# PoE_Injector.net
KiCad netlist of a schematic drawn in Altium Designer
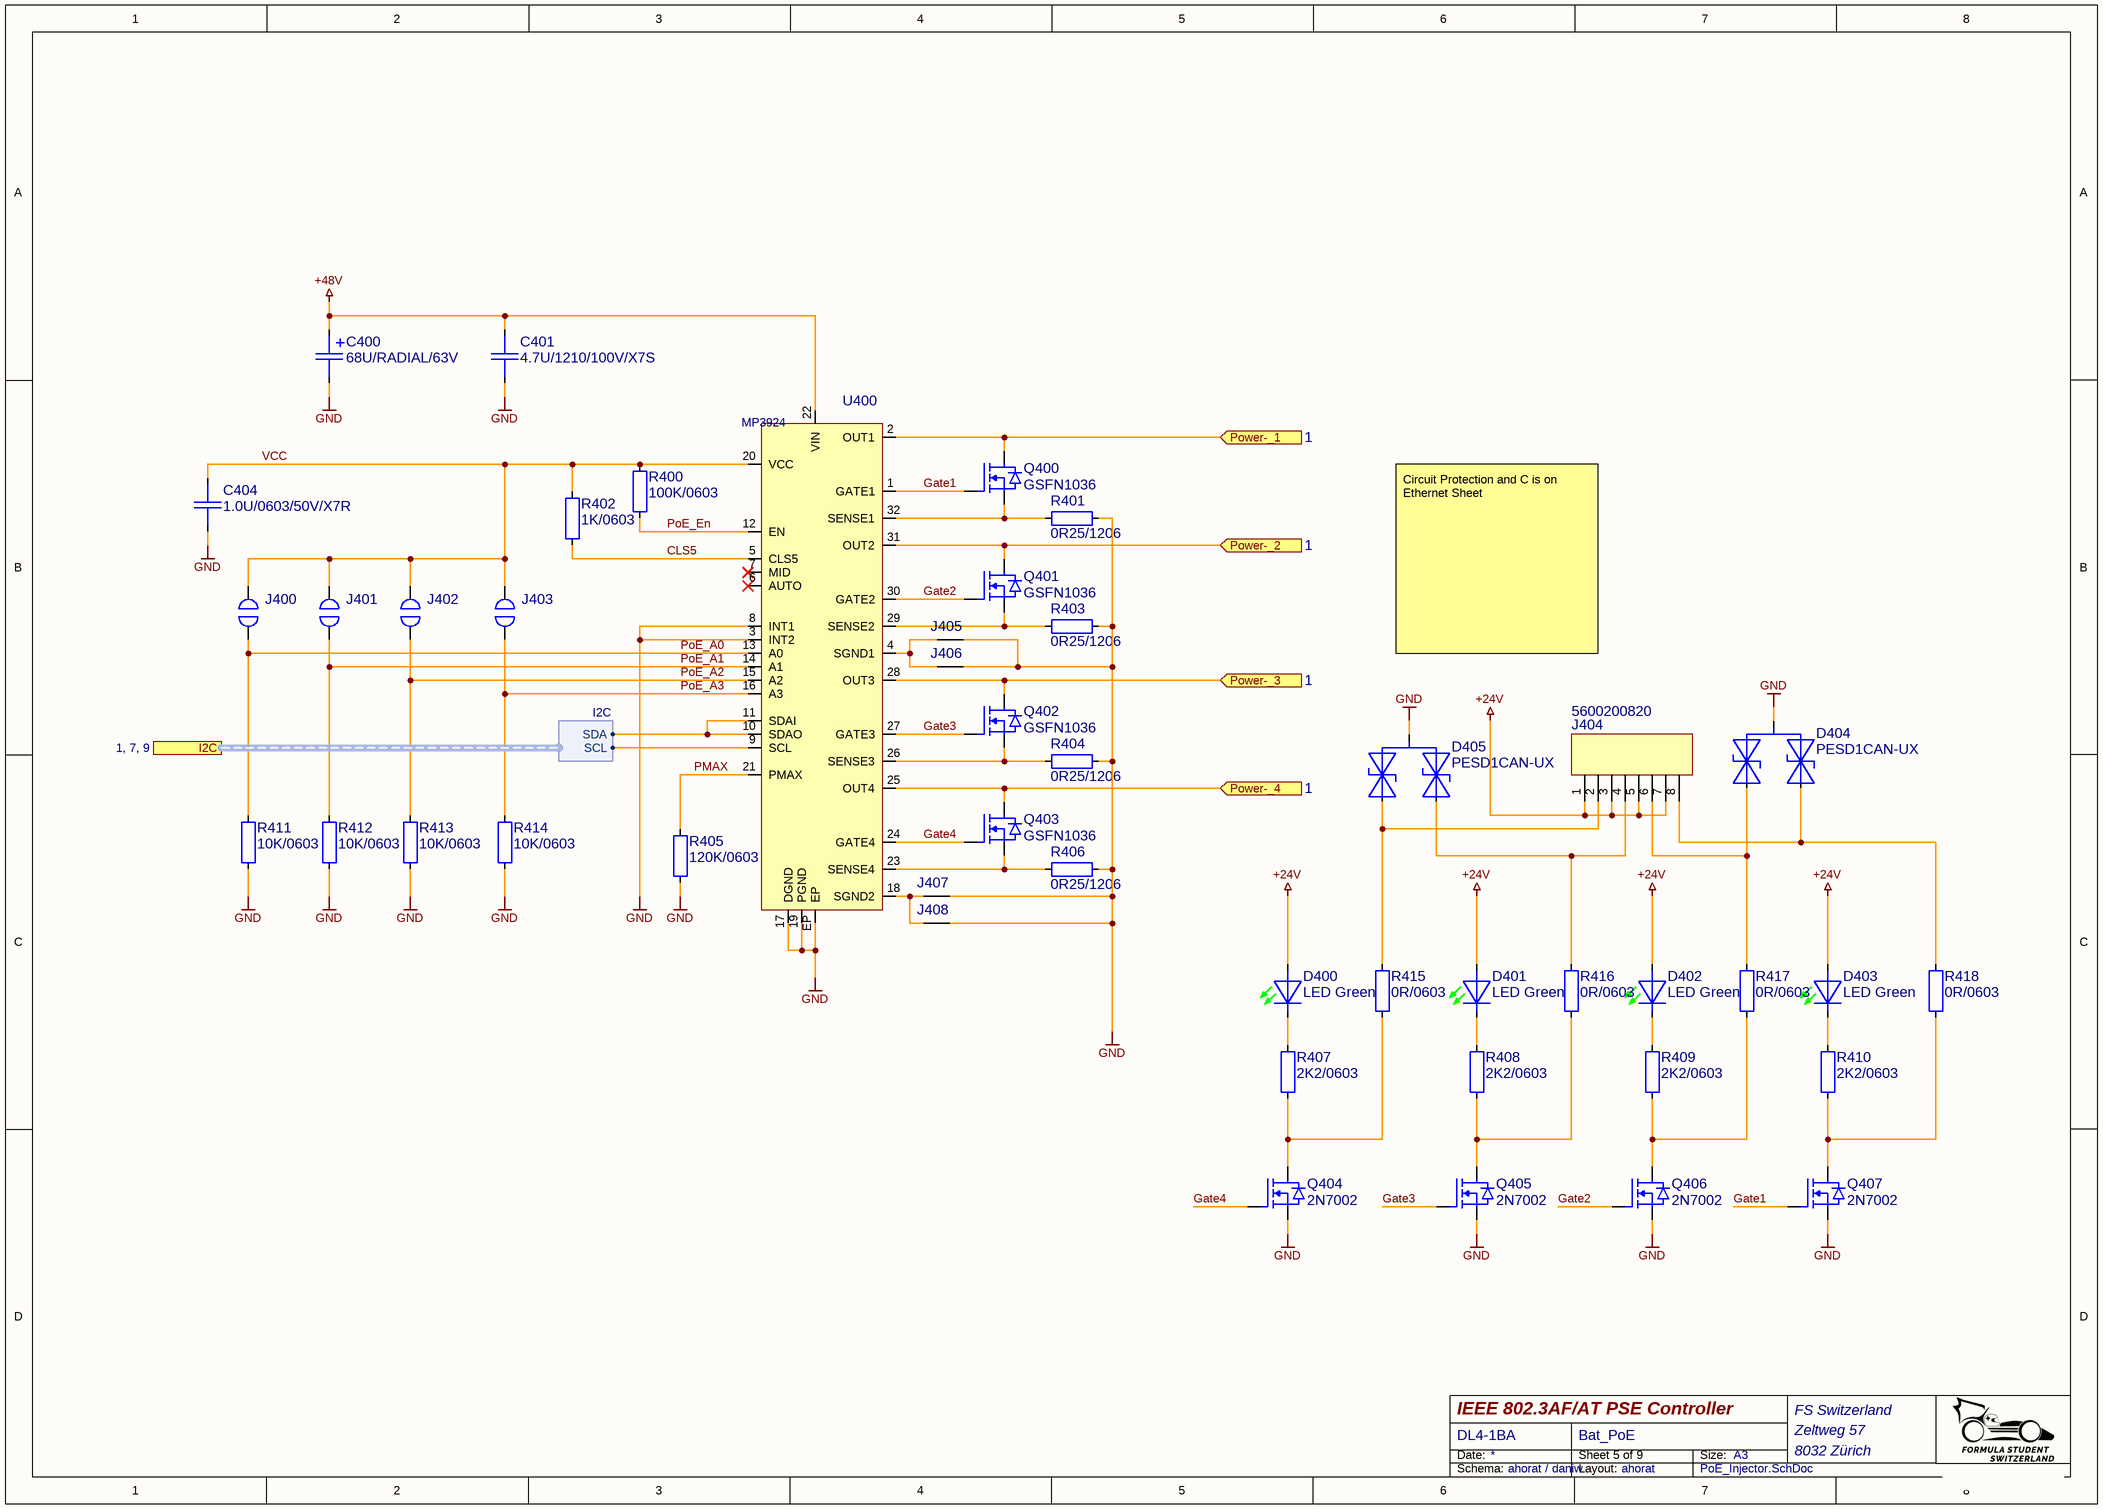
[diagram p0: PoE_Injector.SchDoc]

(export (version "E")
  (design (tool "Eeschema 10.0.6"))
  (components
    (comp (ref "C400")
      (value "68U/RADIAL/63V")
      (footprint "CAP350P80X130")
      (description "CAP THT 8C130 68UF ELKO 63V")
      (fields (field (name "MANUFACTURER") "GENERIC"))
      (libsource (lib "daniw_altium_lib") (part "C_ELEC"))
    )
    (comp (ref "C401")
      (value "4.7U/1210/100V/X7S")
      (footprint "CAP1210_X7R")
      (description "CAP SM 1210 4.7uF 100V X7S")
      (fields (field (name "MANUFACTURER") "GENERIC"))
      (libsource (lib "daniw_altium_lib") (part "C"))
    )
    (comp (ref "C404")
      (value "1.0U/0603/50V/X7R")
      (footprint "CAP0603_X7R")
      (description "CAP SM 0603 1.0uF 50V X7R")
      (fields (field (name "MANUFACTURER") "GENERIC"))
      (libsource (lib "daniw_altium_lib") (part "C"))
    )
    (comp (ref "D400")
      (value "LED Green")
      (footprint "LED0603_GREEN")
      (description "Generic LED Green 0603")
      (fields (field (name "PART NUMBER") "LED Green 0603") (field (name "MANUFACTURER") "GENERIC"))
      (libsource (lib "daniw_altium_lib") (part "LED_GREEN"))
    )
    (comp (ref "D401")
      (value "LED Green")
      (footprint "LED0603_GREEN")
      (description "Generic LED Green 0603")
      (fields (field (name "PART NUMBER") "LED Green 0603") (field (name "MANUFACTURER") "GENERIC"))
      (libsource (lib "daniw_altium_lib") (part "LED_GREEN"))
    )
    (comp (ref "D402")
      (value "LED Green")
      (footprint "LED0603_GREEN")
      (description "Generic LED Green 0603")
      (fields (field (name "PART NUMBER") "LED Green 0603") (field (name "MANUFACTURER") "GENERIC"))
      (libsource (lib "daniw_altium_lib") (part "LED_GREEN"))
    )
    (comp (ref "D403")
      (value "LED Green")
      (footprint "LED0603_GREEN")
      (description "Generic LED Green 0603")
      (fields (field (name "PART NUMBER") "LED Green 0603") (field (name "MANUFACTURER") "GENERIC"))
      (libsource (lib "daniw_altium_lib") (part "LED_GREEN"))
    )
    (comp (ref "D404")
      (value "PESD1CAN-UX")
      (footprint "SOT65P210X95-3-SE")
      (description "CAN bus ESD protection diode")
      (fields (field (name "MANUFACTURER") "Nexperia USA Inc."))
      (libsource (lib "daniw_altium_lib") (part "D_TVS_BIDIR_DUAL"))
    )
    (comp (ref "D405")
      (value "PESD1CAN-UX")
      (footprint "SOT65P210X95-3-SE")
      (description "CAN bus ESD protection diode")
      (fields (field (name "MANUFACTURER") "Nexperia USA Inc."))
      (libsource (lib "daniw_altium_lib") (part "D_TVS_BIDIR_DUAL"))
    )
    (comp (ref "J400")
      (value "Solder Jumper 2pin 0.2mm small")
      (footprint "Solder_Jumper_2pin_0.2mm_small")
      (description "Solder jumper with two pins with a spacing of 0.2mm")
      (fields
        (field (name "PART NUMBER") "Solder_Jumper_2pin_0.2mm_small")
        (field (name "MANUFACTURER") "NONE")
      )
      (libsource (lib "daniw_altium_lib") (part "SolderJumper_2"))
    )
    (comp (ref "J401")
      (value "Solder Jumper 2pin 0.2mm small")
      (footprint "Solder_Jumper_2pin_0.2mm_small")
      (description "Solder jumper with two pins with a spacing of 0.2mm")
      (fields
        (field (name "PART NUMBER") "Solder_Jumper_2pin_0.2mm_small")
        (field (name "MANUFACTURER") "NONE")
      )
      (libsource (lib "daniw_altium_lib") (part "SolderJumper_2"))
    )
    (comp (ref "J402")
      (value "Solder Jumper 2pin 0.2mm small")
      (footprint "Solder_Jumper_2pin_0.2mm_small")
      (description "Solder jumper with two pins with a spacing of 0.2mm")
      (fields
        (field (name "PART NUMBER") "Solder_Jumper_2pin_0.2mm_small")
        (field (name "MANUFACTURER") "NONE")
      )
      (libsource (lib "daniw_altium_lib") (part "SolderJumper_2"))
    )
    (comp (ref "J403")
      (value "Solder Jumper 2pin 0.2mm small")
      (footprint "Solder_Jumper_2pin_0.2mm_small")
      (description "Solder jumper with two pins with a spacing of 0.2mm")
      (fields
        (field (name "PART NUMBER") "Solder_Jumper_2pin_0.2mm_small")
        (field (name "MANUFACTURER") "NONE")
      )
      (libsource (lib "daniw_altium_lib") (part "SolderJumper_2"))
    )
    (comp (ref "J404")
      (value "5600200820")
      (footprint "5600200820")
      (description "DuraClik Wire-to-Board Header, Single Row, Vertical, 8 Circuits, Tin (Sn) Over Nickel, Natural")
      (fields (field (name "PART NUMBER") "DuraClick_1x8_VERT_SMD") (field (name "MANUFACTURER") "Molex"))
      (libsource (lib "daniw_altium_lib") (part "CON8"))
    )
    (comp (ref "J405")
      (value "NETTIE_025x050")
      (footprint "NETTIE_025x050")
      (fields (field (name "MANUFACTURER") "NONE"))
      (libsource (lib "daniw_altium_lib") (part "Nettie"))
    )
    (comp (ref "J406")
      (value "NETTIE_025x050")
      (footprint "NETTIE_025x050")
      (fields (field (name "MANUFACTURER") "NONE"))
      (libsource (lib "daniw_altium_lib") (part "Nettie"))
    )
    (comp (ref "J407")
      (value "NETTIE_025x050")
      (footprint "NETTIE_025x050")
      (fields (field (name "MANUFACTURER") "NONE"))
      (libsource (lib "daniw_altium_lib") (part "Nettie"))
    )
    (comp (ref "J408")
      (value "NETTIE_025x050")
      (footprint "NETTIE_025x050")
      (fields (field (name "MANUFACTURER") "NONE"))
      (libsource (lib "daniw_altium_lib") (part "Nettie"))
    )
    (comp (ref "Q400")
      (value "GSFN1036")
      (footprint "SON065P330X330X075-5-TH245X175")
      (description "N-Kanal 100 V 35 A (Tc) 52W (Tc) Oberflächenmontage 8-PPAK (3,1x3,05)")
      (fields (field (name "MANUFACTURER") "Good-Ark Semiconductor"))
      (libsource (lib "daniw_altium_lib") (part "MOSFET N"))
    )
    (comp (ref "Q401")
      (value "GSFN1036")
      (footprint "SON065P330X330X075-5-TH245X175")
      (description "N-Kanal 100 V 35 A (Tc) 52W (Tc) Oberflächenmontage 8-PPAK (3,1x3,05)")
      (fields (field (name "MANUFACTURER") "Good-Ark Semiconductor"))
      (libsource (lib "daniw_altium_lib") (part "MOSFET N"))
    )
    (comp (ref "Q402")
      (value "GSFN1036")
      (footprint "SON065P330X330X075-5-TH245X175")
      (description "N-Kanal 100 V 35 A (Tc) 52W (Tc) Oberflächenmontage 8-PPAK (3,1x3,05)")
      (fields (field (name "MANUFACTURER") "Good-Ark Semiconductor"))
      (libsource (lib "daniw_altium_lib") (part "MOSFET N"))
    )
    (comp (ref "Q403")
      (value "GSFN1036")
      (footprint "SON065P330X330X075-5-TH245X175")
      (description "N-Kanal 100 V 35 A (Tc) 52W (Tc) Oberflächenmontage 8-PPAK (3,1x3,05)")
      (fields (field (name "MANUFACTURER") "Good-Ark Semiconductor"))
      (libsource (lib "daniw_altium_lib") (part "MOSFET N"))
    )
    (comp (ref "Q404")
      (value "2N7002")
      (footprint "SOT2395P280X125-3-SE")
      (description "60V 115mA 1.2Ω@10V,500mA 200mW 2.1V@250uA N Channel SOT-23 MOSFETs")
      (fields (field (name "MANUFACTURER") "GENERIC"))
      (libsource (lib "daniw_altium_lib") (part "MOSFET N_SOT23"))
    )
    (comp (ref "Q405")
      (value "2N7002")
      (footprint "SOT2395P280X125-3-SE")
      (description "60V 115mA 1.2Ω@10V,500mA 200mW 2.1V@250uA N Channel SOT-23 MOSFETs")
      (fields (field (name "MANUFACTURER") "GENERIC"))
      (libsource (lib "daniw_altium_lib") (part "MOSFET N_SOT23"))
    )
    (comp (ref "Q406")
      (value "2N7002")
      (footprint "SOT2395P280X125-3-SE")
      (description "60V 115mA 1.2Ω@10V,500mA 200mW 2.1V@250uA N Channel SOT-23 MOSFETs")
      (fields (field (name "MANUFACTURER") "GENERIC"))
      (libsource (lib "daniw_altium_lib") (part "MOSFET N_SOT23"))
    )
    (comp (ref "Q407")
      (value "2N7002")
      (footprint "SOT2395P280X125-3-SE")
      (description "60V 115mA 1.2Ω@10V,500mA 200mW 2.1V@250uA N Channel SOT-23 MOSFETs")
      (fields (field (name "MANUFACTURER") "GENERIC"))
      (libsource (lib "daniw_altium_lib") (part "MOSFET N_SOT23"))
    )
    (comp (ref "R400")
      (value "100K/0603")
      (footprint "R0603-0.40-WW")
      (description "RES SM 0603 100K")
      (fields (field (name "MANUFACTURER") "GENERIC"))
      (libsource (lib "daniw_altium_lib") (part "R"))
    )
    (comp (ref "R401")
      (value "0R25/1206")
      (footprint "R1206-0.80-WW")
      (description "RES SM 1206 0R25")
      (fields (field (name "MANUFACTURER") "GENERIC"))
      (libsource (lib "daniw_altium_lib") (part "R"))
    )
    (comp (ref "R402")
      (value "1K/0603")
      (footprint "R0603-0.40-WW")
      (description "RES SM 0603 1K")
      (fields (field (name "MANUFACTURER") "GENERIC"))
      (libsource (lib "daniw_altium_lib") (part "R"))
    )
    (comp (ref "R403")
      (value "0R25/1206")
      (footprint "R1206-0.80-WW")
      (description "RES SM 1206 0R25")
      (fields (field (name "MANUFACTURER") "GENERIC"))
      (libsource (lib "daniw_altium_lib") (part "R"))
    )
    (comp (ref "R404")
      (value "0R25/1206")
      (footprint "R1206-0.80-WW")
      (description "RES SM 1206 0R25")
      (fields (field (name "MANUFACTURER") "GENERIC"))
      (libsource (lib "daniw_altium_lib") (part "R"))
    )
    (comp (ref "R405")
      (value "120K/0603")
      (footprint "R0603-0.40-WW")
      (description "RES SM 0603 120K")
      (fields (field (name "MANUFACTURER") "GENERIC"))
      (libsource (lib "daniw_altium_lib") (part "R"))
    )
    (comp (ref "R406")
      (value "0R25/1206")
      (footprint "R1206-0.80-WW")
      (description "RES SM 1206 0R25")
      (fields (field (name "MANUFACTURER") "GENERIC"))
      (libsource (lib "daniw_altium_lib") (part "R"))
    )
    (comp (ref "R407")
      (value "2K2/0603")
      (footprint "R0603-0.40-WW")
      (description "RES SM 0603 2K2")
      (fields (field (name "MANUFACTURER") "GENERIC"))
      (libsource (lib "daniw_altium_lib") (part "R"))
    )
    (comp (ref "R408")
      (value "2K2/0603")
      (footprint "R0603-0.40-WW")
      (description "RES SM 0603 2K2")
      (fields (field (name "MANUFACTURER") "GENERIC"))
      (libsource (lib "daniw_altium_lib") (part "R"))
    )
    (comp (ref "R409")
      (value "2K2/0603")
      (footprint "R0603-0.40-WW")
      (description "RES SM 0603 2K2")
      (fields (field (name "MANUFACTURER") "GENERIC"))
      (libsource (lib "daniw_altium_lib") (part "R"))
    )
    (comp (ref "R410")
      (value "2K2/0603")
      (footprint "R0603-0.40-WW")
      (description "RES SM 0603 2K2")
      (fields (field (name "MANUFACTURER") "GENERIC"))
      (libsource (lib "daniw_altium_lib") (part "R"))
    )
    (comp (ref "R411")
      (value "10K/0603")
      (footprint "R0603-0.40-WW")
      (description "RES SM 0603 10K")
      (fields (field (name "MANUFACTURER") "GENERIC"))
      (libsource (lib "daniw_altium_lib") (part "R"))
    )
    (comp (ref "R412")
      (value "10K/0603")
      (footprint "R0603-0.40-WW")
      (description "RES SM 0603 10K")
      (fields (field (name "MANUFACTURER") "GENERIC"))
      (libsource (lib "daniw_altium_lib") (part "R"))
    )
    (comp (ref "R413")
      (value "10K/0603")
      (footprint "R0603-0.40-WW")
      (description "RES SM 0603 10K")
      (fields (field (name "MANUFACTURER") "GENERIC"))
      (libsource (lib "daniw_altium_lib") (part "R"))
    )
    (comp (ref "R414")
      (value "10K/0603")
      (footprint "R0603-0.40-WW")
      (description "RES SM 0603 10K")
      (fields (field (name "MANUFACTURER") "GENERIC"))
      (libsource (lib "daniw_altium_lib") (part "R"))
    )
    (comp (ref "R415")
      (value "0R/0603")
      (footprint "R0603-0.40-WW")
      (description "RES SM 0603 0R")
      (fields (field (name "MANUFACTURER") "GENERIC"))
      (libsource (lib "daniw_altium_lib") (part "R"))
    )
    (comp (ref "R416")
      (value "0R/0603")
      (footprint "R0603-0.40-WW")
      (description "RES SM 0603 0R")
      (fields (field (name "MANUFACTURER") "GENERIC"))
      (libsource (lib "daniw_altium_lib") (part "R"))
    )
    (comp (ref "R417")
      (value "0R/0603")
      (footprint "R0603-0.40-WW")
      (description "RES SM 0603 0R")
      (fields (field (name "MANUFACTURER") "GENERIC"))
      (libsource (lib "daniw_altium_lib") (part "R"))
    )
    (comp (ref "R418")
      (value "0R/0603")
      (footprint "R0603-0.40-WW")
      (description "RES SM 0603 0R")
      (fields (field (name "MANUFACTURER") "GENERIC"))
      (libsource (lib "daniw_altium_lib") (part "R"))
    )
    (comp (ref "U400")
      (value "MP3924")
      (footprint "QFN050P500X500X100-32-TH360X360")
      (description "Quad-Port, IEEE 802.3af/at PSE Controller for Power over Ethernet")
      (fields (field (name "MANUFACTURER") "MPS"))
      (libsource (lib "daniw_altium_lib") (part "MP3924"))
    )
  )
  (nets
    (net (code "2") (name "+24V") (class "Default")
      (node (ref "D400") (pin "2") (pinfunction "2_2") (pintype "passive"))
      (node (ref "D401") (pin "2") (pinfunction "2_2") (pintype "passive"))
      (node (ref "D402") (pin "2") (pinfunction "2_2") (pintype "passive"))
      (node (ref "D403") (pin "2") (pinfunction "2_2") (pintype "passive"))
      (node (ref "J404") (pin "1") (pintype "passive"))
      (node (ref "J404") (pin "3") (pintype "passive"))
      (node (ref "J404") (pin "5") (pintype "passive"))
      (node (ref "J404") (pin "7") (pintype "passive"))
    )
    (net (code "3") (name "+48V") (class "Default")
      (node (ref "C400") (pin "1") (pinfunction "1_1") (pintype "passive"))
      (node (ref "C401") (pin "1") (pinfunction "1_1") (pintype "passive"))
      (node (ref "U400") (pin "22") (pinfunction "VIN_22") (pintype "passive"))
    )
    (net (code "4") (name "/CLS5") (class "Default")
      (node (ref "R402") (pin "2") (pinfunction "2_2") (pintype "passive"))
      (node (ref "U400") (pin "5") (pinfunction "CLS5_5") (pintype "passive"))
    )
    (net (code "5") (name "/Gate1") (class "Default")
      (node (ref "Q400") (pin "G") (pinfunction "GATE_G") (pintype "passive"))
      (node (ref "Q407") (pin "1") (pinfunction "GATE_1") (pintype "passive"))
      (node (ref "U400") (pin "1") (pinfunction "GATE1_1") (pintype "passive"))
    )
    (net (code "6") (name "/Gate2") (class "Default")
      (node (ref "Q401") (pin "G") (pinfunction "GATE_G") (pintype "passive"))
      (node (ref "Q406") (pin "1") (pinfunction "GATE_1") (pintype "passive"))
      (node (ref "U400") (pin "30") (pinfunction "GATE2_30") (pintype "passive"))
    )
    (net (code "7") (name "/Gate3") (class "Default")
      (node (ref "Q402") (pin "G") (pinfunction "GATE_G") (pintype "passive"))
      (node (ref "Q405") (pin "1") (pinfunction "GATE_1") (pintype "passive"))
      (node (ref "U400") (pin "27") (pinfunction "GATE3_27") (pintype "passive"))
    )
    (net (code "8") (name "/Gate4") (class "Default")
      (node (ref "Q403") (pin "G") (pinfunction "GATE_G") (pintype "passive"))
      (node (ref "Q404") (pin "1") (pinfunction "GATE_1") (pintype "passive"))
      (node (ref "U400") (pin "24") (pinfunction "GATE4_24") (pintype "passive"))
    )
    (net (code "9") (name "/PMAX") (class "Default")
      (node (ref "R405") (pin "1") (pinfunction "1_1") (pintype "passive"))
      (node (ref "U400") (pin "21") (pinfunction "PMAX_21") (pintype "passive"))
    )
    (net (code "10") (name "/PoE_A0") (class "Default")
      (node (ref "J400") (pin "2") (pinfunction "2_2") (pintype "passive"))
      (node (ref "R411") (pin "1") (pinfunction "1_1") (pintype "passive"))
      (node (ref "U400") (pin "13") (pinfunction "A0_13") (pintype "passive"))
    )
    (net (code "11") (name "/PoE_A1") (class "Default")
      (node (ref "J401") (pin "2") (pinfunction "2_2") (pintype "passive"))
      (node (ref "R412") (pin "1") (pinfunction "1_1") (pintype "passive"))
      (node (ref "U400") (pin "14") (pinfunction "A1_14") (pintype "passive"))
    )
    (net (code "12") (name "/PoE_A2") (class "Default")
      (node (ref "J402") (pin "2") (pinfunction "2_2") (pintype "passive"))
      (node (ref "R413") (pin "1") (pinfunction "1_1") (pintype "passive"))
      (node (ref "U400") (pin "15") (pinfunction "A2_15") (pintype "passive"))
    )
    (net (code "13") (name "/PoE_A3") (class "Default")
      (node (ref "J403") (pin "2") (pinfunction "2_2") (pintype "passive"))
      (node (ref "R414") (pin "1") (pinfunction "1_1") (pintype "passive"))
      (node (ref "U400") (pin "16") (pinfunction "A3_16") (pintype "passive"))
    )
    (net (code "14") (name "/PoE_En") (class "Default")
      (node (ref "R400") (pin "2") (pinfunction "2_2") (pintype "passive"))
      (node (ref "U400") (pin "12") (pinfunction "EN_12") (pintype "passive"))
    )
    (net (code "15") (name "/Power-_1") (class "Default")
      (node (ref "Q400") (pin "D") (pinfunction "DRAIN_D") (pintype "passive"))
      (node (ref "U400") (pin "2") (pinfunction "OUT1_2") (pintype "passive"))
    )
    (net (code "16") (name "/Power-_2") (class "Default")
      (node (ref "Q401") (pin "D") (pinfunction "DRAIN_D") (pintype "passive"))
      (node (ref "U400") (pin "31") (pinfunction "OUT2_31") (pintype "passive"))
    )
    (net (code "17") (name "/Power-_3") (class "Default")
      (node (ref "Q402") (pin "D") (pinfunction "DRAIN_D") (pintype "passive"))
      (node (ref "U400") (pin "28") (pinfunction "OUT3_28") (pintype "passive"))
    )
    (net (code "18") (name "/Power-_4") (class "Default")
      (node (ref "Q403") (pin "D") (pinfunction "DRAIN_D") (pintype "passive"))
      (node (ref "U400") (pin "25") (pinfunction "OUT4_25") (pintype "passive"))
    )
    (net (code "19") (name "/SCL") (class "Default")
      (node (ref "U400") (pin "9") (pinfunction "SCL_9") (pintype "passive"))
    )
    (net (code "20") (name "/SDA") (class "Default")
      (node (ref "U400") (pin "10") (pinfunction "SDAO_10") (pintype "passive"))
      (node (ref "U400") (pin "11") (pinfunction "SDAI_11") (pintype "passive"))
    )
    (net (code "21") (name "/VCC") (class "Default")
      (node (ref "C404") (pin "1") (pinfunction "1_1") (pintype "passive"))
      (node (ref "J400") (pin "1") (pinfunction "1_1") (pintype "passive"))
      (node (ref "J401") (pin "1") (pinfunction "1_1") (pintype "passive"))
      (node (ref "J402") (pin "1") (pinfunction "1_1") (pintype "passive"))
      (node (ref "J403") (pin "1") (pinfunction "1_1") (pintype "passive"))
      (node (ref "R400") (pin "1") (pinfunction "1_1") (pintype "passive"))
      (node (ref "R402") (pin "1") (pinfunction "1_1") (pintype "passive"))
      (node (ref "U400") (pin "20") (pinfunction "VCC_20") (pintype "passive"))
    )
    (net (code "23") (name "GND") (class "Default")
      (node (ref "C400") (pin "2") (pinfunction "2_2") (pintype "passive"))
      (node (ref "C401") (pin "2") (pinfunction "2_2") (pintype "passive"))
      (node (ref "C404") (pin "2") (pinfunction "2_2") (pintype "passive"))
      (node (ref "D404") (pin "3") (pinfunction "3_3") (pintype "passive"))
      (node (ref "D405") (pin "3") (pinfunction "3_3") (pintype "passive"))
      (node (ref "J405") (pin "2") (pinfunction "2_2") (pintype "passive"))
      (node (ref "J406") (pin "2") (pinfunction "2_2") (pintype "passive"))
      (node (ref "J407") (pin "2") (pinfunction "2_2") (pintype "passive"))
      (node (ref "J408") (pin "2") (pinfunction "2_2") (pintype "passive"))
      (node (ref "Q404") (pin "2") (pinfunction "SOURCE_2") (pintype "passive"))
      (node (ref "Q405") (pin "2") (pinfunction "SOURCE_2") (pintype "passive"))
      (node (ref "Q406") (pin "2") (pinfunction "SOURCE_2") (pintype "passive"))
      (node (ref "Q407") (pin "2") (pinfunction "SOURCE_2") (pintype "passive"))
      (node (ref "R401") (pin "2") (pinfunction "2_2") (pintype "passive"))
      (node (ref "R403") (pin "2") (pinfunction "2_2") (pintype "passive"))
      (node (ref "R404") (pin "2") (pinfunction "2_2") (pintype "passive"))
      (node (ref "R405") (pin "2") (pinfunction "2_2") (pintype "passive"))
      (node (ref "R406") (pin "2") (pinfunction "2_2") (pintype "passive"))
      (node (ref "R411") (pin "2") (pinfunction "2_2") (pintype "passive"))
      (node (ref "R412") (pin "2") (pinfunction "2_2") (pintype "passive"))
      (node (ref "R413") (pin "2") (pinfunction "2_2") (pintype "passive"))
      (node (ref "R414") (pin "2") (pinfunction "2_2") (pintype "passive"))
      (node (ref "U400") (pin "17") (pinfunction "DGND_17") (pintype "passive"))
      (node (ref "U400") (pin "19") (pinfunction "PGND_19") (pintype "passive"))
      (node (ref "U400") (pin "3") (pinfunction "INT2_3") (pintype "passive"))
      (node (ref "U400") (pin "8") (pinfunction "INT1_8") (pintype "passive"))
      (node (ref "U400") (pin "EP") (pinfunction "EP_EP") (pintype "passive"))
    )
    (net (code "24") (name "Net-(D400-Pad1)") (class "Default")
      (node (ref "D400") (pin "1") (pinfunction "1_1") (pintype "passive"))
      (node (ref "R407") (pin "1") (pinfunction "1_1") (pintype "passive"))
    )
    (net (code "25") (name "Net-(D401-Pad1)") (class "Default")
      (node (ref "D401") (pin "1") (pinfunction "1_1") (pintype "passive"))
      (node (ref "R408") (pin "1") (pinfunction "1_1") (pintype "passive"))
    )
    (net (code "26") (name "Net-(D402-Pad1)") (class "Default")
      (node (ref "D402") (pin "1") (pinfunction "1_1") (pintype "passive"))
      (node (ref "R409") (pin "1") (pinfunction "1_1") (pintype "passive"))
    )
    (net (code "27") (name "Net-(D403-Pad1)") (class "Default")
      (node (ref "D403") (pin "1") (pinfunction "1_1") (pintype "passive"))
      (node (ref "R410") (pin "1") (pinfunction "1_1") (pintype "passive"))
    )
    (net (code "28") (name "Net-(D404-Pad1)") (class "Default")
      (node (ref "D404") (pin "1") (pinfunction "1_1") (pintype "passive"))
      (node (ref "J404") (pin "8") (pintype "passive"))
      (node (ref "R418") (pin "1") (pinfunction "1_1") (pintype "passive"))
    )
    (net (code "29") (name "Net-(D404-Pad2)") (class "Default")
      (node (ref "D404") (pin "2") (pinfunction "2_2") (pintype "passive"))
      (node (ref "J404") (pin "6") (pintype "passive"))
      (node (ref "R417") (pin "1") (pinfunction "1_1") (pintype "passive"))
    )
    (net (code "30") (name "Net-(D405-Pad1)") (class "Default")
      (node (ref "D405") (pin "1") (pinfunction "1_1") (pintype "passive"))
      (node (ref "J404") (pin "4") (pintype "passive"))
      (node (ref "R416") (pin "1") (pinfunction "1_1") (pintype "passive"))
    )
    (net (code "31") (name "Net-(D405-Pad2)") (class "Default")
      (node (ref "D405") (pin "2") (pinfunction "2_2") (pintype "passive"))
      (node (ref "J404") (pin "2") (pintype "passive"))
      (node (ref "R415") (pin "1") (pinfunction "1_1") (pintype "passive"))
    )
    (net (code "32") (name "Net-(Q400-SOURCE)") (class "Default")
      (node (ref "Q400") (pin "S") (pinfunction "SOURCE_S") (pintype "passive"))
      (node (ref "R401") (pin "1") (pinfunction "1_1") (pintype "passive"))
      (node (ref "U400") (pin "32") (pinfunction "SENSE1_32") (pintype "passive"))
    )
    (net (code "33") (name "Net-(Q401-SOURCE)") (class "Default")
      (node (ref "Q401") (pin "S") (pinfunction "SOURCE_S") (pintype "passive"))
      (node (ref "R403") (pin "1") (pinfunction "1_1") (pintype "passive"))
      (node (ref "U400") (pin "29") (pinfunction "SENSE2_29") (pintype "passive"))
    )
    (net (code "34") (name "Net-(Q402-SOURCE)") (class "Default")
      (node (ref "Q402") (pin "S") (pinfunction "SOURCE_S") (pintype "passive"))
      (node (ref "R404") (pin "1") (pinfunction "1_1") (pintype "passive"))
      (node (ref "U400") (pin "26") (pinfunction "SENSE3_26") (pintype "passive"))
    )
    (net (code "35") (name "Net-(Q403-SOURCE)") (class "Default")
      (node (ref "Q403") (pin "S") (pinfunction "SOURCE_S") (pintype "passive"))
      (node (ref "R406") (pin "1") (pinfunction "1_1") (pintype "passive"))
      (node (ref "U400") (pin "23") (pinfunction "SENSE4_23") (pintype "passive"))
    )
    (net (code "36") (name "Net-(Q404-DRAIN)") (class "Default")
      (node (ref "Q404") (pin "3") (pinfunction "DRAIN_3") (pintype "passive"))
      (node (ref "R407") (pin "2") (pinfunction "2_2") (pintype "passive"))
      (node (ref "R415") (pin "2") (pinfunction "2_2") (pintype "passive"))
    )
    (net (code "37") (name "Net-(Q405-DRAIN)") (class "Default")
      (node (ref "Q405") (pin "3") (pinfunction "DRAIN_3") (pintype "passive"))
      (node (ref "R408") (pin "2") (pinfunction "2_2") (pintype "passive"))
      (node (ref "R416") (pin "2") (pinfunction "2_2") (pintype "passive"))
    )
    (net (code "38") (name "Net-(Q406-DRAIN)") (class "Default")
      (node (ref "Q406") (pin "3") (pinfunction "DRAIN_3") (pintype "passive"))
      (node (ref "R409") (pin "2") (pinfunction "2_2") (pintype "passive"))
      (node (ref "R417") (pin "2") (pinfunction "2_2") (pintype "passive"))
    )
    (net (code "39") (name "Net-(Q407-DRAIN)") (class "Default")
      (node (ref "Q407") (pin "3") (pinfunction "DRAIN_3") (pintype "passive"))
      (node (ref "R410") (pin "2") (pinfunction "2_2") (pintype "passive"))
      (node (ref "R418") (pin "2") (pinfunction "2_2") (pintype "passive"))
    )
    (net (code "40") (name "Net-(U400-SGND1)") (class "Default")
      (node (ref "J405") (pin "1") (pinfunction "1_1") (pintype "passive"))
      (node (ref "J406") (pin "1") (pinfunction "1_1") (pintype "passive"))
      (node (ref "U400") (pin "4") (pinfunction "SGND1_4") (pintype "passive"))
    )
    (net (code "41") (name "Net-(U400-SGND2)") (class "Default")
      (node (ref "J407") (pin "1") (pinfunction "1_1") (pintype "passive"))
      (node (ref "J408") (pin "1") (pinfunction "1_1") (pintype "passive"))
      (node (ref "U400") (pin "18") (pinfunction "SGND2_18") (pintype "passive"))
    )
    (net (code "42") (name "unconnected-(U400-AUTO-Pad6)") (class "Default")
      (node (ref "U400") (pin "6") (pinfunction "AUTO_6") (pintype "passive+no_connect"))
    )
    (net (code "43") (name "unconnected-(U400-MID-Pad7)") (class "Default")
      (node (ref "U400") (pin "7") (pinfunction "MID_7") (pintype "passive+no_connect"))
    )
  )
)
